# IoT_Greenhouse_V1_0_A_-_Esp32.net
KiCad netlist of a schematic drawn in Altium Designer
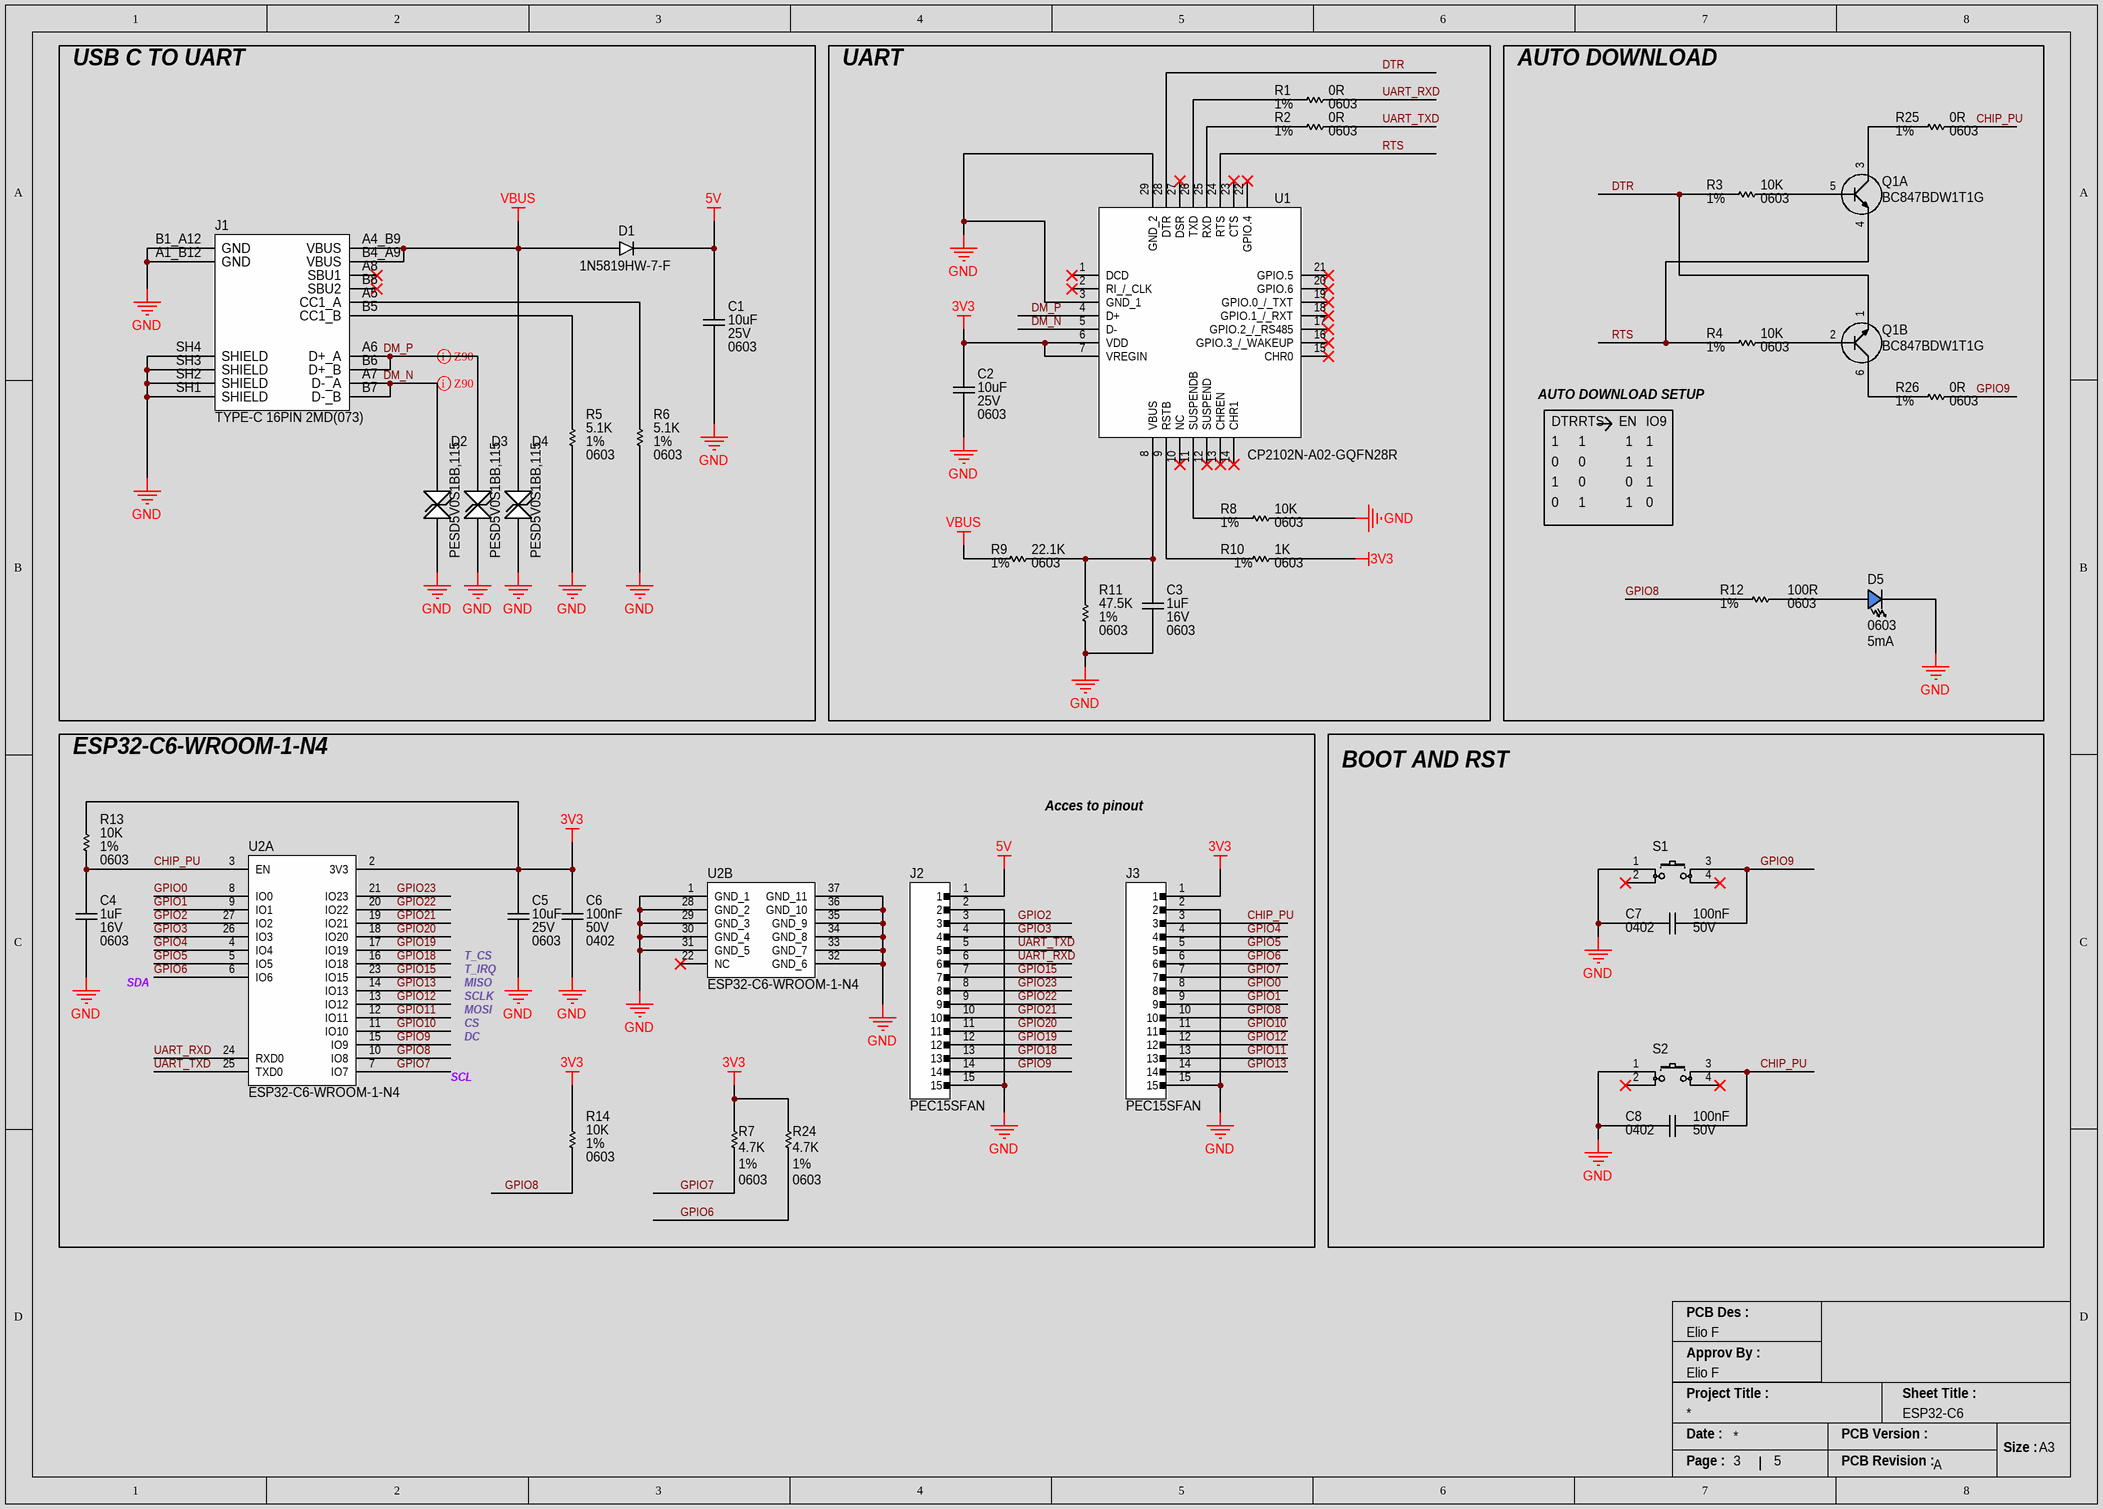
[diagram p0: IoT_Greenhouse V1.0 A - Esp32.SchDoc]

(export (version "E")
  (design (tool "Eeschema 10.0.6"))
  (components
    (comp (ref "C1")
      (value "GRM188R61E106MA73D")
      (footprint "CAP_0603_CAPC1608X08N")
      (description "Multilayer Ceramic Capacitor, 10 uF, 25 V, ± 20%, X5R, 0603 [1608 Metric]")
      (fields
        (field (name "MANUFACTURER") "Murata")
        (field (name "TOLERANCE") "20%")
        (field (name "CASE/PACKAGE") "0603")
        (field (name "CAPACITANCE") "10uF")
        (field (name "VOLTAGE RATING") "25V")
      )
      (libsource (lib "Electronic Devices_LIB") (part "CAP_10UF_25V_X5R_0603"))
    )
    (comp (ref "C2")
      (value "GRM188R61E106MA73D")
      (footprint "CAP_0603_CAPC1608X08N")
      (description "Multilayer Ceramic Capacitor, 10 uF, 25 V, ± 20%, X5R, 0603 [1608 Metric]")
      (fields
        (field (name "MANUFACTURER") "Murata")
        (field (name "TOLERANCE") "20%")
        (field (name "CASE/PACKAGE") "0603")
        (field (name "CAPACITANCE") "10uF")
        (field (name "VOLTAGE RATING") "25V")
      )
      (libsource (lib "Electronic Devices_LIB") (part "CAP_10UF_25V_X5R_0603"))
    )
    (comp (ref "C3")
      (value "CL10A105KO8NNNC")
      (footprint "CAP_0603_CAPC1608X08N")
      (description "CAP CER 1UF 16V X5R 0603")
      (fields
        (field (name "MANUFACTURER") "Samsung")
        (field (name "TOLERANCE") "10%")
        (field (name "VOLTAGE RATING") "16V")
        (field (name "CAPACITANCE") "1uF")
        (field (name "CASE/PACKAGE") "0603")
      )
      (libsource (lib "Electronic Devices_LIB") (part "CAP_1UF_16V_X5R_0603"))
    )
    (comp (ref "C4")
      (value "CL10A105KO8NNNC")
      (footprint "CAP_0603_CAPC1608X08N")
      (description "CAP CER 1UF 16V X5R 0603")
      (fields
        (field (name "MANUFACTURER") "Samsung")
        (field (name "TOLERANCE") "10%")
        (field (name "VOLTAGE RATING") "16V")
        (field (name "CAPACITANCE") "1uF")
        (field (name "CASE/PACKAGE") "0603")
      )
      (libsource (lib "Electronic Devices_LIB") (part "CAP_1UF_16V_X5R_0603"))
    )
    (comp (ref "C5")
      (value "GRM188R61E106MA73D")
      (footprint "CAP_0603_CAPC1608X08N")
      (description "Multilayer Ceramic Capacitor, 10 uF, 25 V, ± 20%, X5R, 0603 [1608 Metric]")
      (fields
        (field (name "MANUFACTURER") "Murata")
        (field (name "TOLERANCE") "20%")
        (field (name "CASE/PACKAGE") "0603")
        (field (name "CAPACITANCE") "10uF")
        (field (name "VOLTAGE RATING") "25V")
      )
      (libsource (lib "Electronic Devices_LIB") (part "CAP_10UF_25V_X5R_0603"))
    )
    (comp (ref "C6")
      (value "GRM155R71H104KE14D")
      (footprint "CAP_0402_CAPC1005X05N")
      (description "Multilayer Ceramic Capacitor, 0.1 uF, 16 V, ± 10%, X7R, 0402 [1005 Metric]")
      (fields
        (field (name "MANUFACTURER") "Murata")
        (field (name "TOLERANCE") "10%")
        (field (name "VOLTAGE RATING") "50V")
        (field (name "CAPACITANCE") "100nF")
        (field (name "CASE/PACKAGE") "0402")
      )
      (libsource (lib "Electronic Devices_LIB") (part "CAP_100NF_50V_X7R_0402"))
    )
    (comp (ref "C7")
      (value "GRM155R71H104KE14D")
      (footprint "CAP_0402_CAPC1005X05N")
      (description "Multilayer Ceramic Capacitor, 0.1 uF, 16 V, ± 10%, X7R, 0402 [1005 Metric]")
      (fields
        (field (name "MANUFACTURER") "Murata")
        (field (name "TOLERANCE") "10%")
        (field (name "VOLTAGE RATING") "50V")
        (field (name "CAPACITANCE") "100nF")
        (field (name "CASE/PACKAGE") "0402")
      )
      (libsource (lib "Electronic Devices_LIB") (part "CAP_100NF_50V_X7R_0402"))
    )
    (comp (ref "C8")
      (value "GRM155R71H104KE14D")
      (footprint "CAP_0402_CAPC1005X05N")
      (description "Multilayer Ceramic Capacitor, 0.1 uF, 16 V, ± 10%, X7R, 0402 [1005 Metric]")
      (fields
        (field (name "MANUFACTURER") "Murata")
        (field (name "TOLERANCE") "10%")
        (field (name "VOLTAGE RATING") "50V")
        (field (name "CAPACITANCE") "100nF")
        (field (name "CASE/PACKAGE") "0402")
      )
      (libsource (lib "Electronic Devices_LIB") (part "CAP_100NF_50V_X7R_0402"))
    )
    (comp (ref "D1")
      (value "1N5819HW-7-F")
      (footprint "DIO_SOD3716X145N")
      (description "Rectifier Diode, Schottky, 1 Phase, 1 Element, 1A, 40V V(RRM), Silicon")
      (fields (field (name "MANUFACTURER") "Diodes"))
      (libsource (lib "Electronic Devices_LIB") (part "DIO_RECT_40V_1A_1N5819HW-7-F"))
    )
    (comp (ref "D2")
      (value "PESD5V0S1BB,115")
      (footprint "DIO_TVS_SODFL1608X65N")
      (description "ESD Suppressor Diode TVS Bi-Dir 5V Automotive 2-Pin SOD-523 T/R / TVS DIODE 5VWM 14VC SOD523")
      (fields (field (name "MANUFACTURER") "Nexperia"))
      (libsource (lib "Electronic Devices_LIB") (part "DIO_TVS_BID_5V_PESD5V0S1BB,115"))
    )
    (comp (ref "D3")
      (value "PESD5V0S1BB,115")
      (footprint "DIO_TVS_SODFL1608X65N")
      (description "ESD Suppressor Diode TVS Bi-Dir 5V Automotive 2-Pin SOD-523 T/R / TVS DIODE 5VWM 14VC SOD523")
      (fields (field (name "MANUFACTURER") "Nexperia"))
      (libsource (lib "Electronic Devices_LIB") (part "DIO_TVS_BID_5V_PESD5V0S1BB,115"))
    )
    (comp (ref "D4")
      (value "PESD5V0S1BB,115")
      (footprint "DIO_TVS_SODFL1608X65N")
      (description "ESD Suppressor Diode TVS Bi-Dir 5V Automotive 2-Pin SOD-523 T/R / TVS DIODE 5VWM 14VC SOD523")
      (fields (field (name "MANUFACTURER") "Nexperia"))
      (libsource (lib "Electronic Devices_LIB") (part "DIO_TVS_BID_5V_PESD5V0S1BB,115"))
    )
    (comp (ref "D5")
      (value "LTST-C193TBKT-5A")
      (footprint "LED_0603-BLUE-0.75mm")
      (description "LED Uni-Color Blue 468nm 2-Pin Chip LED T/R")
      (fields
        (field (name "MANUFACTURER") "Vishay Lite-On")
        (field (name "CASE CODE (IMPERIAL)") "0603")
        (field (name "TEST CURRENT") "5mA")
      )
      (libsource (lib "Electronic Devices_LIB") (part "LED_DIO_BLUE_5mA_0603"))
    )
    (comp (ref "J1")
      (value "TYPE-C 16PIN 2MD(073)")
      (footprint "CONN_USB_C_16P")
      (description "5A 1 Surface Mount 16P Female -25℃~+85℃ Type-C SMD USB Connectors ROHS")
      (fields (field (name "MANUFACTURER") "SHOU HAN"))
      (libsource (lib "Electronic Devices_LIB") (part "CONN_USB_TYPEC_2.0_16P_TYPE-C 16PIN 2MD(073)"))
    )
    (comp (ref "J2")
      (value "PEC15SFAN")
      (footprint "HEADER_MALE_15P")
      (description "CONN HEADER .100 SINGL STR 15POS")
      (fields (field (name "MANUFACTURER") "Sullins"))
      (libsource (lib "Electronic Devices_LIB") (part "CONN_HEADER_MALE_15P_2.54mm"))
    )
    (comp (ref "J3")
      (value "PEC15SFAN")
      (footprint "HEADER_MALE_15P")
      (description "CONN HEADER .100 SINGL STR 15POS")
      (fields (field (name "MANUFACTURER") "Sullins"))
      (libsource (lib "Electronic Devices_LIB") (part "CONN_HEADER_MALE_15P_2.54mm"))
    )
    (comp (ref "Q1")
      (value "BC847BDW1T1G")
      (footprint "TRANS_BJT_SOT65P210X110-6N")
      (description "ON Semi BC847BDW1T1G Dual NPN Bipolar Transistor; 0.1 A; 45 V; 6-Pin SC-88")
      (fields (field (name "MANUFACTURER") "ON Semiconductor"))
      (libsource (lib "Electronic Devices_LIB") (part "TRANS_BIPOLAR_NPN_BC847BDW1T1G"))
    )
    (comp (ref "R1")
      (value "RC0603FR-070RL")
      (footprint "RES_0603_RESC1608X04N")
      (description "RC Series 0603 0.1 W 0 Ohm Jumper Surface Mount Thick Film Chip Resistor")
      (fields
        (field (name "MANUFACTURER") "Yageo")
        (field (name "TOLERANCE") "1%")
        (field (name "RESISTANCE") "0R")
        (field (name "CASE CODE (IMPERIAL)") "0603")
      )
      (libsource (lib "Electronic Devices_LIB") (part "RES_0R_1%_100mW_0603"))
    )
    (comp (ref "R2")
      (value "RC0603FR-070RL")
      (footprint "RES_0603_RESC1608X04N")
      (description "RC Series 0603 0.1 W 0 Ohm Jumper Surface Mount Thick Film Chip Resistor")
      (fields
        (field (name "MANUFACTURER") "Yageo")
        (field (name "TOLERANCE") "1%")
        (field (name "RESISTANCE") "0R")
        (field (name "CASE CODE (IMPERIAL)") "0603")
      )
      (libsource (lib "Electronic Devices_LIB") (part "RES_0R_1%_100mW_0603"))
    )
    (comp (ref "R3")
      (value "AC0603FR-1010KL")
      (footprint "RES_0603_RESC1608X04N")
      (description "Chip Resistor Automotive Grade Thick Film 0603 10kOhm 1% Paper T/R")
      (fields
        (field (name "MANUFACTURER") "Yageo")
        (field (name "RESISTANCE") "10K")
        (field (name "TOLERANCE") "1%")
        (field (name "CASE/PACKAGE") "0603")
      )
      (libsource (lib "Electronic Devices_LIB") (part "RES_10K_1%_100mW_0603"))
    )
    (comp (ref "R4")
      (value "AC0603FR-1010KL")
      (footprint "RES_0603_RESC1608X04N")
      (description "Chip Resistor Automotive Grade Thick Film 0603 10kOhm 1% Paper T/R")
      (fields
        (field (name "MANUFACTURER") "Yageo")
        (field (name "RESISTANCE") "10K")
        (field (name "TOLERANCE") "1%")
        (field (name "CASE/PACKAGE") "0603")
      )
      (libsource (lib "Electronic Devices_LIB") (part "RES_10K_1%_100mW_0603"))
    )
    (comp (ref "R5")
      (value "RC0603FR-075K1L")
      (footprint "RES_0603_RESC1608X04N")
      (description "SMD Chip Resistor, 5.1 kOhm, ± 1%, 100 mW, 0603 [1608 Metric], Thick Film, General Purpose")
      (fields
        (field (name "MANUFACTURER") "Yageo")
        (field (name "TOLERANCE") "1%")
        (field (name "RESISTANCE") "5.1K")
        (field (name "CASE/PACKAGE") "0603")
      )
      (libsource (lib "Electronic Devices_LIB") (part "RES_5.1K_1%_100mW_0603"))
    )
    (comp (ref "R6")
      (value "RC0603FR-075K1L")
      (footprint "RES_0603_RESC1608X04N")
      (description "SMD Chip Resistor, 5.1 kOhm, ± 1%, 100 mW, 0603 [1608 Metric], Thick Film, General Purpose")
      (fields
        (field (name "MANUFACTURER") "Yageo")
        (field (name "TOLERANCE") "1%")
        (field (name "RESISTANCE") "5.1K")
        (field (name "CASE/PACKAGE") "0603")
      )
      (libsource (lib "Electronic Devices_LIB") (part "RES_5.1K_1%_100mW_0603"))
    )
    (comp (ref "R7")
      (value "RC0603FR-074K7L")
      (footprint "RES_0603_RESC1608X04N")
      (description "Res Thick Film 0603 4.7K Ohm 1% 1/10W ±100ppm/°C Molded SMD Paper T/R")
      (fields
        (field (name "MANUFACTURER") "Yageo")
        (field (name "RESISTANCE") "4.7K")
        (field (name "TOLERANCE") "1%")
        (field (name "CASE/PACKAGE") "0603")
      )
      (libsource (lib "Electronic Devices_LIB") (part "RES_4.7K_1%_100mW_0603"))
    )
    (comp (ref "R8")
      (value "AC0603FR-1010KL")
      (footprint "RES_0603_RESC1608X04N")
      (description "Chip Resistor Automotive Grade Thick Film 0603 10kOhm 1% Paper T/R")
      (fields
        (field (name "MANUFACTURER") "Yageo")
        (field (name "RESISTANCE") "10K")
        (field (name "TOLERANCE") "1%")
        (field (name "CASE/PACKAGE") "0603")
      )
      (libsource (lib "Electronic Devices_LIB") (part "RES_10K_1%_100mW_0603"))
    )
    (comp (ref "R9")
      (value "RC0603FR-0722K1L")
      (footprint "RES_0603_RESC1608X04N")
      (description "SMD Chip Resistor, 22.1 kOhm, ± 1%, 100 mW, 0603 [1608 Metric], Thick Film, General Purpose")
      (fields
        (field (name "MANUFACTURER") "Yageo")
        (field (name "RESISTANCE") "22.1K")
        (field (name "TOLERANCE") "1%")
        (field (name "CASE/PACKAGE") "0603")
      )
      (libsource (lib "Electronic Devices_LIB") (part "RES_22.1K_1%_100mW_0603"))
    )
    (comp (ref "R10")
      (value "AC0603FR-101KL")
      (footprint "RES_0603_RESC1608X04N")
      (description "Chip Resistor Automotive Grade Thick Film 0603 1kOhm 1% Paper T/R")
      (fields
        (field (name "MANUFACTURER") "Yageo")
        (field (name "RESISTANCE") "1K")
        (field (name "TOLERANCE") "1%")
        (field (name "CASE/PACKAGE") "0603")
      )
      (libsource (lib "Electronic Devices_LIB") (part "RES_1K_1%_100mW_0603"))
    )
    (comp (ref "R11")
      (value "AC0603FR-0747K5L")
      (footprint "RES_0603_RESC1608X04N")
      (description "SMD Chip Resistor, 47.5 kOhm, ± 1%, 100 mW, 0603 [1608 Metric], Thick Film, General Purpose")
      (fields
        (field (name "MANUFACTURER") "Yageo")
        (field (name "TOLERANCE") "1%")
        (field (name "RESISTANCE") "47.5K")
        (field (name "CASE/PACKAGE") "0603")
      )
      (libsource (lib "Electronic Devices_LIB") (part "RES_47.5K_1%_100mW_0603"))
    )
    (comp (ref "R12")
      (value "ERJ3EKF1000V")
      (footprint "CAP_0603_CAPC1608X08N")
      (description "Res Thick Film 0603 100 Ohm 1% 1/10W ±100ppm/°C Molded SMD Punched Carrier T/R")
      (fields
        (field (name "MANUFACTURER") "Panasonic")
        (field (name "CASE CODE (IMPERIAL)") "0603")
        (field (name "TOLERANCE") "1%")
        (field (name "RESISTANCE") "100R")
      )
      (libsource (lib "Electronic Devices_LIB") (part "RES_100R_1%_100MW_0603"))
    )
    (comp (ref "R13")
      (value "AC0603FR-1010KL")
      (footprint "RES_0603_RESC1608X04N")
      (description "Chip Resistor Automotive Grade Thick Film 0603 10kOhm 1% Paper T/R")
      (fields
        (field (name "MANUFACTURER") "Yageo")
        (field (name "RESISTANCE") "10K")
        (field (name "TOLERANCE") "1%")
        (field (name "CASE/PACKAGE") "0603")
      )
      (libsource (lib "Electronic Devices_LIB") (part "RES_10K_1%_100mW_0603"))
    )
    (comp (ref "R14")
      (value "AC0603FR-1010KL")
      (footprint "RES_0603_RESC1608X04N")
      (description "Chip Resistor Automotive Grade Thick Film 0603 10kOhm 1% Paper T/R")
      (fields
        (field (name "MANUFACTURER") "Yageo")
        (field (name "RESISTANCE") "10K")
        (field (name "TOLERANCE") "1%")
        (field (name "CASE/PACKAGE") "0603")
      )
      (libsource (lib "Electronic Devices_LIB") (part "RES_10K_1%_100mW_0603"))
    )
    (comp (ref "R24")
      (value "RC0603FR-074K7L")
      (footprint "RES_0603_RESC1608X04N")
      (description "Res Thick Film 0603 4.7K Ohm 1% 1/10W ±100ppm/°C Molded SMD Paper T/R")
      (fields
        (field (name "MANUFACTURER") "Yageo")
        (field (name "RESISTANCE") "4.7K")
        (field (name "TOLERANCE") "1%")
        (field (name "CASE/PACKAGE") "0603")
      )
      (libsource (lib "Electronic Devices_LIB") (part "RES_4.7K_1%_100mW_0603"))
    )
    (comp (ref "R25")
      (value "RC0603FR-070RL")
      (footprint "RES_0603_RESC1608X04N")
      (description "RC Series 0603 0.1 W 0 Ohm Jumper Surface Mount Thick Film Chip Resistor")
      (fields
        (field (name "MANUFACTURER") "Yageo")
        (field (name "TOLERANCE") "1%")
        (field (name "RESISTANCE") "0R")
        (field (name "CASE CODE (IMPERIAL)") "0603")
      )
      (libsource (lib "Electronic Devices_LIB") (part "RES_0R_1%_100mW_0603"))
    )
    (comp (ref "R26")
      (value "RC0603FR-070RL")
      (footprint "RES_0603_RESC1608X04N")
      (description "RC Series 0603 0.1 W 0 Ohm Jumper Surface Mount Thick Film Chip Resistor")
      (fields
        (field (name "MANUFACTURER") "Yageo")
        (field (name "TOLERANCE") "1%")
        (field (name "RESISTANCE") "0R")
        (field (name "CASE CODE (IMPERIAL)") "0603")
      )
      (libsource (lib "Electronic Devices_LIB") (part "RES_0R_1%_100mW_0603"))
    )
    (comp (ref "S1")
      (value "PTS526SK15SMTR2LFS")
      (footprint "SWT_NO_PTS526SK15SMTR2LFS")
      (description "Switch Tactile N.O. SPST Round Button Gull Wing 0.05A 12VDC 200000Cycles 2.55N SMD T/R")
      (fields (field (name "MANUFACTURER") "ITT C&K"))
      (libsource (lib "Electronic Devices_LIB") (part "SWITCH_NO_SPST_0.05A"))
    )
    (comp (ref "S2")
      (value "PTS526SK15SMTR2LFS")
      (footprint "SWT_NO_PTS526SK15SMTR2LFS")
      (description "Switch Tactile N.O. SPST Round Button Gull Wing 0.05A 12VDC 200000Cycles 2.55N SMD T/R")
      (fields (field (name "MANUFACTURER") "ITT C&K"))
      (libsource (lib "Electronic Devices_LIB") (part "SWITCH_NO_SPST_0.05A"))
    )
    (comp (ref "U1")
      (value "CP2102N-A02-GQFN28R")
      (footprint "IC_BRIDGE_UART_QFN50P500X500X80-29N-D")
      (description "Full Speed USB to UART Bridge USB 2.0 3.3V T/R Automotive 28-Pin QFN EP")
      (fields (field (name "MANUFACTURER") "Silicon Labs"))
      (libsource (lib "Electronic Devices_LIB") (part "IC_BRIDGE_UART_CP2102N-A02-GQFN28R"))
    )
    (comp (ref "U2")
      (value "ESP32-C6-WROOM-1-N4")
      (footprint "IC_MODULE_ESP32C6WROOM1N4")
      (description "ESP32-C6-WROOM-1-N4 Engineering Module - 4 MB Quad SPI Flash")
      (fields (field (name "MANUFACTURER") "Espressif Systems"))
      (libsource (lib "Electronic Devices_LIB") (part "IC_MODULE_ESP32-C6-WROOM-1-N4"))
    )
  )
  (nets
    (net (code "1") (name "/CHIP_PU") (class "Default")
      (node (ref "C4") (pin "2") (pinfunction "2_2") (pintype "passive"))
      (node (ref "C8") (pin "1") (pinfunction "1_1") (pintype "passive"))
      (node (ref "J3") (pin "3") (pinfunction "3_3") (pintype "passive"))
      (node (ref "R13") (pin "2") (pinfunction "2_2") (pintype "passive"))
      (node (ref "R25") (pin "1") (pinfunction "1_1") (pintype "passive"))
      (node (ref "S2") (pin "3") (pinfunction "NO1_3") (pintype "passive"))
      (node (ref "U2") (pin "3") (pinfunction "EN_3") (pintype "passive"))
    )
    (net (code "2") (name "/DM_N") (class "Default")
      (node (ref "D2") (pin "2") (pinfunction "K2_2") (pintype "passive"))
      (node (ref "J1") (pin "A7") (pinfunction "D-_A_A7") (pintype "passive"))
      (node (ref "J1") (pin "B7") (pinfunction "D-_B_B7") (pintype "passive"))
      (node (ref "U1") (pin "5") (pinfunction "D-_5") (pintype "passive"))
    )
    (net (code "3") (name "/DM_P") (class "Default")
      (node (ref "D3") (pin "2") (pinfunction "K2_2") (pintype "passive"))
      (node (ref "J1") (pin "A6") (pinfunction "D+_A_A6") (pintype "passive"))
      (node (ref "J1") (pin "B6") (pinfunction "D+_B_B6") (pintype "passive"))
      (node (ref "U1") (pin "4") (pinfunction "D+_4") (pintype "passive"))
    )
    (net (code "4") (name "/DTR") (class "Default")
      (node (ref "Q1") (pin "1") (pinfunction "EMITTER_2_1") (pintype "passive"))
      (node (ref "R3") (pin "2") (pinfunction "2_2") (pintype "passive"))
      (node (ref "U1") (pin "28") (pinfunction "DTR_28") (pintype "passive"))
    )
    (net (code "5") (name "/GPIO0") (class "Default")
      (node (ref "J3") (pin "8") (pinfunction "8_8") (pintype "passive"))
      (node (ref "U2") (pin "8") (pinfunction "IO0_8") (pintype "passive"))
    )
    (net (code "6") (name "/GPIO1") (class "Default")
      (node (ref "J3") (pin "9") (pinfunction "9_9") (pintype "passive"))
      (node (ref "U2") (pin "9") (pinfunction "IO1_9") (pintype "passive"))
    )
    (net (code "7") (name "/GPIO2") (class "Default")
      (node (ref "J2") (pin "3") (pinfunction "3_3") (pintype "passive"))
      (node (ref "U2") (pin "27") (pinfunction "IO2_27") (pintype "passive"))
    )
    (net (code "8") (name "/GPIO3") (class "Default")
      (node (ref "J2") (pin "4") (pinfunction "4_4") (pintype "passive"))
      (node (ref "U2") (pin "26") (pinfunction "IO3_26") (pintype "passive"))
    )
    (net (code "9") (name "/GPIO4") (class "Default")
      (node (ref "J3") (pin "4") (pinfunction "4_4") (pintype "passive"))
      (node (ref "U2") (pin "4") (pinfunction "IO4_4") (pintype "passive"))
    )
    (net (code "10") (name "/GPIO5") (class "Default")
      (node (ref "J3") (pin "5") (pinfunction "5_5") (pintype "passive"))
      (node (ref "U2") (pin "5") (pinfunction "IO5_5") (pintype "passive"))
    )
    (net (code "11") (name "/GPIO6") (class "Default")
      (node (ref "J3") (pin "6") (pinfunction "6_6") (pintype "passive"))
      (node (ref "R24") (pin "1") (pinfunction "1_1") (pintype "passive"))
      (node (ref "U2") (pin "6") (pinfunction "IO6_6") (pintype "passive"))
    )
    (net (code "12") (name "/GPIO7") (class "Default")
      (node (ref "J3") (pin "7") (pinfunction "7_7") (pintype "passive"))
      (node (ref "R7") (pin "1") (pinfunction "1_1") (pintype "passive"))
      (node (ref "U2") (pin "7") (pinfunction "IO7_7") (pintype "passive"))
    )
    (net (code "13") (name "/GPIO8") (class "Default")
      (node (ref "J3") (pin "10") (pinfunction "10_10") (pintype "passive"))
      (node (ref "R12") (pin "1") (pinfunction "1_1") (pintype "passive"))
      (node (ref "R14") (pin "2") (pinfunction "2_2") (pintype "passive"))
      (node (ref "U2") (pin "10") (pinfunction "IO8_10") (pintype "passive"))
    )
    (net (code "14") (name "/GPIO9") (class "Default")
      (node (ref "C7") (pin "1") (pinfunction "1_1") (pintype "passive"))
      (node (ref "J2") (pin "14") (pinfunction "14_14") (pintype "passive"))
      (node (ref "R26") (pin "1") (pinfunction "1_1") (pintype "passive"))
      (node (ref "S1") (pin "3") (pinfunction "NO1_3") (pintype "passive"))
      (node (ref "U2") (pin "15") (pinfunction "IO9_15") (pintype "passive"))
    )
    (net (code "15") (name "/GPIO10") (class "Default")
      (node (ref "J3") (pin "11") (pinfunction "11_11") (pintype "passive"))
      (node (ref "U2") (pin "11") (pinfunction "IO10_11") (pintype "passive"))
    )
    (net (code "16") (name "/GPIO11") (class "Default")
      (node (ref "J3") (pin "13") (pinfunction "13_13") (pintype "passive"))
      (node (ref "U2") (pin "12") (pinfunction "IO11_12") (pintype "passive"))
    )
    (net (code "17") (name "/GPIO12") (class "Default")
      (node (ref "J3") (pin "12") (pinfunction "12_12") (pintype "passive"))
      (node (ref "U2") (pin "13") (pinfunction "IO12_13") (pintype "passive"))
    )
    (net (code "18") (name "/GPIO13") (class "Default")
      (node (ref "J3") (pin "14") (pinfunction "14_14") (pintype "passive"))
      (node (ref "U2") (pin "14") (pinfunction "IO13_14") (pintype "passive"))
    )
    (net (code "19") (name "/GPIO15") (class "Default")
      (node (ref "J2") (pin "7") (pinfunction "7_7") (pintype "passive"))
      (node (ref "U2") (pin "23") (pinfunction "IO15_23") (pintype "passive"))
    )
    (net (code "20") (name "/GPIO18") (class "Default")
      (node (ref "J2") (pin "13") (pinfunction "13_13") (pintype "passive"))
      (node (ref "U2") (pin "16") (pinfunction "IO18_16") (pintype "passive"))
    )
    (net (code "21") (name "/GPIO19") (class "Default")
      (node (ref "J2") (pin "12") (pinfunction "12_12") (pintype "passive"))
      (node (ref "U2") (pin "17") (pinfunction "IO19_17") (pintype "passive"))
    )
    (net (code "22") (name "/GPIO20") (class "Default")
      (node (ref "J2") (pin "11") (pinfunction "11_11") (pintype "passive"))
      (node (ref "U2") (pin "18") (pinfunction "IO20_18") (pintype "passive"))
    )
    (net (code "23") (name "/GPIO21") (class "Default")
      (node (ref "J2") (pin "10") (pinfunction "10_10") (pintype "passive"))
      (node (ref "U2") (pin "19") (pinfunction "IO21_19") (pintype "passive"))
    )
    (net (code "24") (name "/GPIO22") (class "Default")
      (node (ref "J2") (pin "9") (pinfunction "9_9") (pintype "passive"))
      (node (ref "U2") (pin "20") (pinfunction "IO22_20") (pintype "passive"))
    )
    (net (code "25") (name "/GPIO23") (class "Default")
      (node (ref "J2") (pin "8") (pinfunction "8_8") (pintype "passive"))
      (node (ref "U2") (pin "21") (pinfunction "IO23_21") (pintype "passive"))
    )
    (net (code "26") (name "/RTS") (class "Default")
      (node (ref "Q1") (pin "4") (pinfunction "EMITTER_1_4") (pintype "passive"))
      (node (ref "R4") (pin "2") (pinfunction "2_2") (pintype "passive"))
      (node (ref "U1") (pin "24") (pinfunction "RTS_24") (pintype "passive"))
    )
    (net (code "27") (name "/UART_RXD") (class "Default")
      (node (ref "J2") (pin "6") (pinfunction "6_6") (pintype "passive"))
      (node (ref "R1") (pin "1") (pinfunction "1_1") (pintype "passive"))
      (node (ref "U2") (pin "24") (pinfunction "RXD0_24") (pintype "passive"))
    )
    (net (code "28") (name "/UART_TXD") (class "Default")
      (node (ref "J2") (pin "5") (pinfunction "5_5") (pintype "passive"))
      (node (ref "R2") (pin "1") (pinfunction "1_1") (pintype "passive"))
      (node (ref "U2") (pin "25") (pinfunction "TXD0_25") (pintype "passive"))
    )
    (net (code "29") (name "3V3") (class "Default")
      (node (ref "C2") (pin "2") (pinfunction "2_2") (pintype "passive"))
      (node (ref "C5") (pin "2") (pinfunction "2_2") (pintype "passive"))
      (node (ref "C6") (pin "2") (pinfunction "2_2") (pintype "passive"))
      (node (ref "J3") (pin "1") (pinfunction "1_1") (pintype "passive"))
      (node (ref "R10") (pin "2") (pinfunction "2_2") (pintype "passive"))
      (node (ref "R13") (pin "1") (pinfunction "1_1") (pintype "passive"))
      (node (ref "R14") (pin "1") (pinfunction "1_1") (pintype "passive"))
      (node (ref "R24") (pin "2") (pinfunction "2_2") (pintype "passive"))
      (node (ref "R7") (pin "2") (pinfunction "2_2") (pintype "passive"))
      (node (ref "U1") (pin "6") (pinfunction "VDD_6") (pintype "passive"))
      (node (ref "U1") (pin "7") (pinfunction "VREGIN_7") (pintype "passive"))
      (node (ref "U2") (pin "2") (pinfunction "3V3_2") (pintype "passive"))
    )
    (net (code "30") (name "5V") (class "Default")
      (node (ref "C1") (pin "2") (pinfunction "2_2") (pintype "passive"))
      (node (ref "D1") (pin "1") (pinfunction "K_1") (pintype "passive"))
      (node (ref "J2") (pin "1") (pinfunction "1_1") (pintype "passive"))
    )
    (net (code "31") (name "GND") (class "Default")
      (node (ref "C1") (pin "1") (pinfunction "1_1") (pintype "passive"))
      (node (ref "C2") (pin "1") (pinfunction "1_1") (pintype "passive"))
      (node (ref "C3") (pin "1") (pinfunction "1_1") (pintype "passive"))
      (node (ref "C4") (pin "1") (pinfunction "1_1") (pintype "passive"))
      (node (ref "C5") (pin "1") (pinfunction "1_1") (pintype "passive"))
      (node (ref "C6") (pin "1") (pinfunction "1_1") (pintype "passive"))
      (node (ref "C7") (pin "2") (pinfunction "2_2") (pintype "passive"))
      (node (ref "C8") (pin "2") (pinfunction "2_2") (pintype "passive"))
      (node (ref "D2") (pin "1") (pinfunction "K1_1") (pintype "passive"))
      (node (ref "D3") (pin "1") (pinfunction "K1_1") (pintype "passive"))
      (node (ref "D4") (pin "1") (pinfunction "K1_1") (pintype "passive"))
      (node (ref "D5") (pin "1") (pinfunction "C_1") (pintype "passive"))
      (node (ref "J1") (pin "A1_B12") (pinfunction "GND_A1_B12") (pintype "power_in"))
      (node (ref "J1") (pin "B1_A12") (pinfunction "GND_B1_A12") (pintype "power_in"))
      (node (ref "J1") (pin "SH1") (pinfunction "SHIELD_SH1") (pintype "passive"))
      (node (ref "J1") (pin "SH2") (pinfunction "SHIELD_SH2") (pintype "passive"))
      (node (ref "J1") (pin "SH3") (pinfunction "SHIELD_SH3") (pintype "passive"))
      (node (ref "J1") (pin "SH4") (pinfunction "SHIELD_SH4") (pintype "passive"))
      (node (ref "J2") (pin "15") (pinfunction "15_15") (pintype "passive"))
      (node (ref "J2") (pin "2") (pinfunction "2_2") (pintype "passive"))
      (node (ref "J3") (pin "15") (pinfunction "15_15") (pintype "passive"))
      (node (ref "J3") (pin "2") (pinfunction "2_2") (pintype "passive"))
      (node (ref "R11") (pin "1") (pinfunction "1_1") (pintype "passive"))
      (node (ref "R5") (pin "1") (pinfunction "1_1") (pintype "passive"))
      (node (ref "R6") (pin "1") (pinfunction "1_1") (pintype "passive"))
      (node (ref "R8") (pin "2") (pinfunction "2_2") (pintype "passive"))
      (node (ref "S1") (pin "1") (pinfunction "COM_1_1") (pintype "passive"))
      (node (ref "S2") (pin "1") (pinfunction "COM_1_1") (pintype "passive"))
      (node (ref "U1") (pin "29") (pinfunction "GND_2_29") (pintype "passive"))
      (node (ref "U1") (pin "3") (pinfunction "GND_1_3") (pintype "passive"))
      (node (ref "U2") (pin "1") (pinfunction "GND_1_1") (pintype "passive"))
      (node (ref "U2") (pin "28") (pinfunction "GND_2_28") (pintype "passive"))
      (node (ref "U2") (pin "29") (pinfunction "GND_3_29") (pintype "passive"))
      (node (ref "U2") (pin "30") (pinfunction "GND_4_30") (pintype "passive"))
      (node (ref "U2") (pin "31") (pinfunction "GND_5_31") (pintype "passive"))
      (node (ref "U2") (pin "32") (pinfunction "GND_6_32") (pintype "passive"))
      (node (ref "U2") (pin "33") (pinfunction "GND_7_33") (pintype "passive"))
      (node (ref "U2") (pin "34") (pinfunction "GND_8_34") (pintype "passive"))
      (node (ref "U2") (pin "35") (pinfunction "GND_9_35") (pintype "passive"))
      (node (ref "U2") (pin "36") (pinfunction "GND_10_36") (pintype "passive"))
      (node (ref "U2") (pin "37") (pinfunction "GND_11_37") (pintype "passive"))
    )
    (net (code "32") (name "Net-(D5-A)") (class "Default")
      (node (ref "D5") (pin "2") (pinfunction "A_2") (pintype "passive"))
      (node (ref "R12") (pin "2") (pinfunction "2_2") (pintype "passive"))
    )
    (net (code "33") (name "Net-(J1-CC1_A)") (class "Default")
      (node (ref "J1") (pin "A5") (pinfunction "CC1_A_A5") (pintype "passive"))
      (node (ref "R6") (pin "2") (pinfunction "2_2") (pintype "passive"))
    )
    (net (code "34") (name "Net-(J1-CC1_B)") (class "Default")
      (node (ref "J1") (pin "B5") (pinfunction "CC1_B_B5") (pintype "passive"))
      (node (ref "R5") (pin "2") (pinfunction "2_2") (pintype "passive"))
    )
    (net (code "35") (name "Net-(Q1A-BASE_1)") (class "Default")
      (node (ref "Q1") (pin "5") (pinfunction "BASE_1_5") (pintype "passive"))
      (node (ref "R3") (pin "1") (pinfunction "1_1") (pintype "passive"))
    )
    (net (code "36") (name "Net-(Q1A-COLLECTOR_1)") (class "Default")
      (node (ref "Q1") (pin "3") (pinfunction "COLLECTOR_1_3") (pintype "passive"))
      (node (ref "R25") (pin "2") (pinfunction "2_2") (pintype "passive"))
    )
    (net (code "37") (name "Net-(Q1B-BASE_2)") (class "Default")
      (node (ref "Q1") (pin "2") (pinfunction "BASE_2_2") (pintype "passive"))
      (node (ref "R4") (pin "1") (pinfunction "1_1") (pintype "passive"))
    )
    (net (code "38") (name "Net-(Q1B-COLLECTOR_2)") (class "Default")
      (node (ref "Q1") (pin "6") (pinfunction "COLLECTOR_2_6") (pintype "passive"))
      (node (ref "R26") (pin "2") (pinfunction "2_2") (pintype "passive"))
    )
    (net (code "39") (name "Net-(U1-RSTB)") (class "Default")
      (node (ref "R10") (pin "1") (pinfunction "1_1") (pintype "passive"))
      (node (ref "U1") (pin "9") (pinfunction "RSTB_9") (pintype "passive"))
    )
    (net (code "40") (name "Net-(U1-RXD)") (class "Default")
      (node (ref "R2") (pin "2") (pinfunction "2_2") (pintype "passive"))
      (node (ref "U1") (pin "25") (pinfunction "RXD_25") (pintype "passive"))
    )
    (net (code "41") (name "Net-(U1-SUSPENDB)") (class "Default")
      (node (ref "R8") (pin "1") (pinfunction "1_1") (pintype "passive"))
      (node (ref "U1") (pin "11") (pinfunction "SUSPENDB_11") (pintype "passive"))
    )
    (net (code "42") (name "Net-(U1-TXD)") (class "Default")
      (node (ref "R1") (pin "2") (pinfunction "2_2") (pintype "passive"))
      (node (ref "U1") (pin "26") (pinfunction "TXD_26") (pintype "passive"))
    )
    (net (code "43") (name "Net-(U1-VBUS)") (class "Default")
      (node (ref "C3") (pin "2") (pinfunction "2_2") (pintype "passive"))
      (node (ref "R11") (pin "2") (pinfunction "2_2") (pintype "passive"))
      (node (ref "R9") (pin "2") (pinfunction "2_2") (pintype "passive"))
      (node (ref "U1") (pin "8") (pinfunction "VBUS_8") (pintype "passive"))
    )
    (net (code "44") (name "VBUS") (class "Default")
      (node (ref "D1") (pin "2") (pinfunction "A_2") (pintype "passive"))
      (node (ref "D4") (pin "2") (pinfunction "K2_2") (pintype "passive"))
      (node (ref "J1") (pin "A4_B9") (pinfunction "VBUS_A4_B9") (pintype "power_in"))
      (node (ref "J1") (pin "B4_A9") (pinfunction "VBUS_B4_A9") (pintype "power_in"))
      (node (ref "R9") (pin "1") (pinfunction "1_1") (pintype "passive"))
    )
    (net (code "45") (name "unconnected-(J1-SBU1-PadA8)") (class "Default")
      (node (ref "J1") (pin "A8") (pinfunction "SBU1_A8") (pintype "passive+no_connect"))
    )
    (net (code "46") (name "unconnected-(J1-SBU2-PadB8)") (class "Default")
      (node (ref "J1") (pin "B8") (pinfunction "SBU2_B8") (pintype "passive+no_connect"))
    )
    (net (code "47") (name "unconnected-(S1-COM2-Pad2)") (class "Default")
      (node (ref "S1") (pin "2") (pinfunction "COM2_2") (pintype "passive+no_connect"))
    )
    (net (code "48") (name "unconnected-(S1-NO2-Pad4)") (class "Default")
      (node (ref "S1") (pin "4") (pinfunction "NO2_4") (pintype "passive+no_connect"))
    )
    (net (code "49") (name "unconnected-(S2-COM2-Pad2)") (class "Default")
      (node (ref "S2") (pin "2") (pinfunction "COM2_2") (pintype "passive+no_connect"))
    )
    (net (code "50") (name "unconnected-(S2-NO2-Pad4)") (class "Default")
      (node (ref "S2") (pin "4") (pinfunction "NO2_4") (pintype "passive+no_connect"))
    )
    (net (code "51") (name "unconnected-(U1-CHR0-Pad15)") (class "Default")
      (node (ref "U1") (pin "15") (pinfunction "CHR0_15") (pintype "passive+no_connect"))
    )
    (net (code "52") (name "unconnected-(U1-CHR1-Pad14)") (class "Default")
      (node (ref "U1") (pin "14") (pinfunction "CHR1_14") (pintype "passive+no_connect"))
    )
    (net (code "53") (name "unconnected-(U1-CHREN-Pad13)") (class "Default")
      (node (ref "U1") (pin "13") (pinfunction "CHREN_13") (pintype "passive+no_connect"))
    )
    (net (code "54") (name "unconnected-(U1-CTS-Pad23)") (class "Default")
      (node (ref "U1") (pin "23") (pinfunction "CTS_23") (pintype "passive+no_connect"))
    )
    (net (code "55") (name "unconnected-(U1-DCD-Pad1)") (class "Default")
      (node (ref "U1") (pin "1") (pinfunction "DCD_1") (pintype "passive+no_connect"))
    )
    (net (code "56") (name "unconnected-(U1-DSR-Pad27)") (class "Default")
      (node (ref "U1") (pin "27") (pinfunction "DSR_27") (pintype "passive+no_connect"))
    )
    (net (code "57") (name "unconnected-(U1-GPIO.0_{slash}_TXT-Pad19)") (class "Default")
      (node (ref "U1") (pin "19") (pinfunction "GPIO.0_/_TXT_19") (pintype "passive+no_connect"))
    )
    (net (code "58") (name "unconnected-(U1-GPIO.1_{slash}_RXT-Pad18)") (class "Default")
      (node (ref "U1") (pin "18") (pinfunction "GPIO.1_/_RXT_18") (pintype "passive+no_connect"))
    )
    (net (code "59") (name "unconnected-(U1-GPIO.2_{slash}_RS485-Pad17)") (class "Default")
      (node (ref "U1") (pin "17") (pinfunction "GPIO.2_/_RS485_17") (pintype "passive+no_connect"))
    )
    (net (code "60") (name "unconnected-(U1-GPIO.3_{slash}_WAKEUP-Pad16)") (class "Default")
      (node (ref "U1") (pin "16") (pinfunction "GPIO.3_/_WAKEUP_16") (pintype "passive+no_connect"))
    )
    (net (code "61") (name "unconnected-(U1-GPIO.4-Pad22)") (class "Default")
      (node (ref "U1") (pin "22") (pinfunction "GPIO.4_22") (pintype "passive+no_connect"))
    )
    (net (code "62") (name "unconnected-(U1-GPIO.5-Pad21)") (class "Default")
      (node (ref "U1") (pin "21") (pinfunction "GPIO.5_21") (pintype "passive+no_connect"))
    )
    (net (code "63") (name "unconnected-(U1-GPIO.6-Pad20)") (class "Default")
      (node (ref "U1") (pin "20") (pinfunction "GPIO.6_20") (pintype "passive+no_connect"))
    )
    (net (code "64") (name "unconnected-(U1-NC-Pad10)") (class "Default")
      (node (ref "U1") (pin "10") (pinfunction "NC_10") (pintype "passive+no_connect"))
    )
    (net (code "65") (name "unconnected-(U1-RI_{slash}_CLK-Pad2)") (class "Default")
      (node (ref "U1") (pin "2") (pinfunction "RI_/_CLK_2") (pintype "passive+no_connect"))
    )
    (net (code "66") (name "unconnected-(U1-SUSPEND-Pad12)") (class "Default")
      (node (ref "U1") (pin "12") (pinfunction "SUSPEND_12") (pintype "passive+no_connect"))
    )
    (net (code "67") (name "unconnected-(U2B-NC-Pad22)") (class "Default")
      (node (ref "U2") (pin "22") (pinfunction "NC_22") (pintype "passive+no_connect"))
    )
  )
)
